# serial_port.net
KiCad netlist of a schematic drawn in Altium Designer
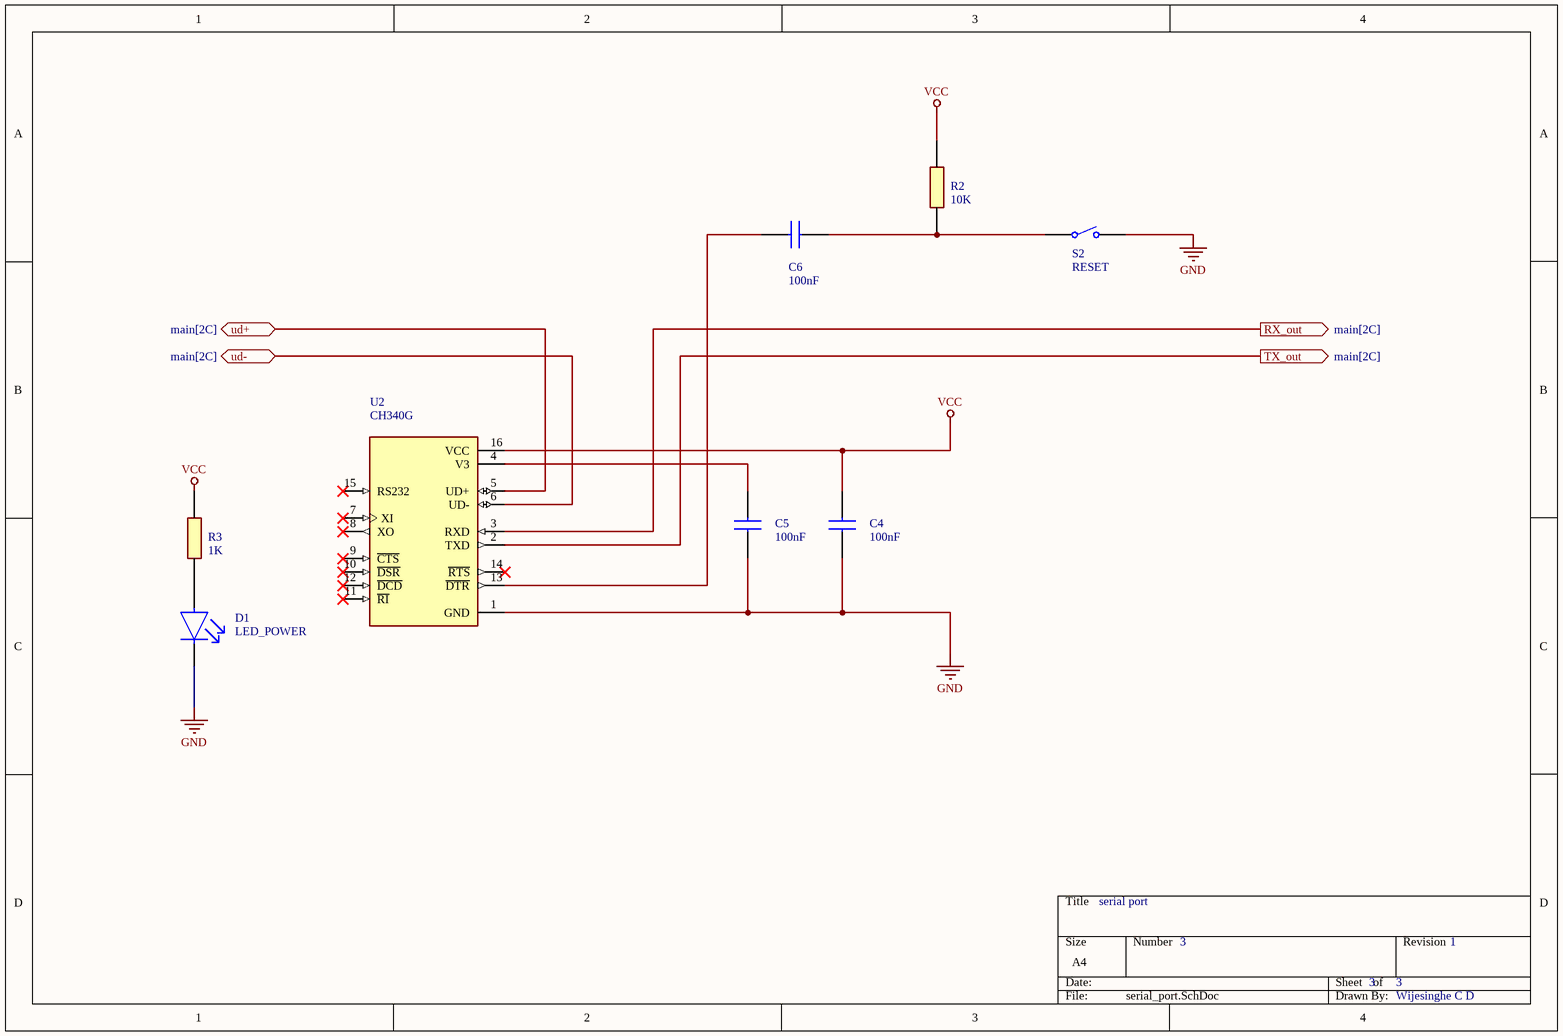
[diagram p0: serial_port.SchDoc]

(export (version "E")
  (design (tool "Eeschema 10.0.6"))
  (components
    (comp (ref "C4")
      (value "100nF")
      (footprint "SamacSys:CAPC1608X90N")
      (description "Capacitor")
      (fields
        (field (name "MANUFACTURER_PART_NUMBER") "CL10B104JB8NNNC")
        (field (name "MOUSER PART NUMBER") "187-CL10B104JB8NNNC")
      )
      (libsource (lib "*") (part "CL10B104JB8NNNC"))
    )
    (comp (ref "C5")
      (value "100nF")
      (footprint "SamacSys:CAPC1608X90N")
      (description "Capacitor")
      (fields
        (field (name "MANUFACTURER_PART_NUMBER") "CL10B104JB8NNNC")
        (field (name "MOUSER PART NUMBER") "187-CL10B104JB8NNNC")
      )
      (libsource (lib "*") (part "CL10B104JB8NNNC"))
    )
    (comp (ref "C6")
      (value "100nF")
      (footprint "SamacSys:CAPC1608X90N")
      (description "Capacitor")
      (fields
        (field (name "MANUFACTURER_PART_NUMBER") "CL10B104JB8NNNC")
        (field (name "MOUSER PART NUMBER") "187-CL10B104JB8NNNC")
      )
      (libsource (lib "*") (part "CL10B104JB8NNNC"))
    )
    (comp (ref "D1")
      (value "LED_POWER")
      (footprint "FP-LTST-C190GKT-MFG")
      (description "LED GREEN CLEAR CHIP SMD")
      (fields (field (name "VOLTAGE") "2V"))
      (libsource (lib "Altium Content Vault") (part "8706943c75ba83719d021d2fdc84c58"))
    )
    (comp (ref "R2")
      (value "10K")
      (footprint "SamacSys:RESC2012X75N")
      (description "Resistor")
      (fields
        (field (name "MANUFACTURER_PART_NUMBER") "ERJ-P6WF1002V")
        (field (name "MOUSER PART NUMBER") "667-ERJ-P6WF1002V")
      )
      (libsource (lib "*") (part "ERJ-P6WF1002V"))
    )
    (comp (ref "R3")
      (value "1K")
      (footprint "SamacSys:RESC2012X75N")
      (description "Resistor")
      (fields
        (field (name "MANUFACTURER_PART_NUMBER") "ERJ-P6WF1002V")
        (field (name "MOUSER PART NUMBER") "667-ERJ-P6WF1002V")
      )
      (libsource (lib "*") (part "ERJ-P6WF1002V"))
    )
    (comp (ref "S2")
      (value "RESET")
      (footprint "TECO-FSMSM-2_V")
      (description "FSMSM Push Button Switch, 50 mA, -35 to 85 degC, 2-Pin SMD, RoHS, Bulk")
      (fields (field (name "MANUFACTURER") "TE Connectivity"))
      (libsource (lib "Altium Content Vault") (part "SW-SPST-2_C"))
    )
    (comp (ref "U2")
      (value "CH340G")
      (footprint "SOIC127P600X180-16N")
      (description "USB Interface Integrated Circuit")
      (fields (field (name "MP") "Ch340G") (field (name "MF") "WCH"))
      (libsource (lib "CH340G") (part "CH340G"))
    )
  )
  (nets
    (net (code "1") (name "/RX_out") (class "Default")
      (node (ref "U2") (pin "3") (pinfunction "RXD_3") (pintype "input"))
    )
    (net (code "2") (name "/TX_out") (class "Default")
      (node (ref "U2") (pin "2") (pinfunction "TXD_2") (pintype "output"))
    )
    (net (code "3") (name "/ud+") (class "Default")
      (node (ref "U2") (pin "5") (pinfunction "UD+_5") (pintype "bidirectional"))
    )
    (net (code "4") (name "/ud-") (class "Default")
      (node (ref "U2") (pin "6") (pinfunction "UD-_6") (pintype "bidirectional"))
    )
    (net (code "5") (name "GND") (class "Default")
      (node (ref "C4") (pin "2") (pinfunction "2_2") (pintype "passive"))
      (node (ref "C5") (pin "2") (pinfunction "2_2") (pintype "passive"))
      (node (ref "D1") (pin "1") (pinfunction "C_1") (pintype "passive"))
      (node (ref "S2") (pin "2") (pinfunction "2_2") (pintype "passive"))
      (node (ref "U2") (pin "1") (pinfunction "GND_1") (pintype "power_in"))
    )
    (net (code "6") (name "Net-(C6-Pad2)") (class "Default")
      (node (ref "C6") (pin "2") (pinfunction "2_2") (pintype "passive"))
      (node (ref "R2") (pin "1") (pinfunction "1_1") (pintype "passive"))
      (node (ref "S2") (pin "1") (pinfunction "1_1") (pintype "passive"))
    )
    (net (code "7") (name "Net-(D1-A)") (class "Default")
      (node (ref "D1") (pin "2") (pinfunction "A_2") (pintype "passive"))
      (node (ref "R3") (pin "1") (pinfunction "1_1") (pintype "passive"))
    )
    (net (code "8") (name "Net-(U2-V3)") (class "Default")
      (node (ref "C5") (pin "1") (pinfunction "1_1") (pintype "passive"))
      (node (ref "U2") (pin "4") (pinfunction "V3_4") (pintype "power_in"))
    )
    (net (code "9") (name "Net-(U2-~{DTR})") (class "Default")
      (node (ref "C6") (pin "1") (pinfunction "1_1") (pintype "passive"))
      (node (ref "U2") (pin "13") (pinfunction "~{DTR}_13") (pintype "output"))
    )
    (net (code "10") (name "VCC") (class "Default")
      (node (ref "C4") (pin "1") (pinfunction "1_1") (pintype "passive"))
      (node (ref "R2") (pin "2") (pinfunction "2_2") (pintype "passive"))
      (node (ref "R3") (pin "2") (pinfunction "2_2") (pintype "passive"))
      (node (ref "U2") (pin "16") (pinfunction "VCC_16") (pintype "power_in"))
    )
    (net (code "11") (name "unconnected-(U2-RS232-Pad15)") (class "Default")
      (node (ref "U2") (pin "15") (pinfunction "RS232_15") (pintype "input+no_connect"))
    )
    (net (code "12") (name "unconnected-(U2-XI-Pad7)") (class "Default")
      (node (ref "U2") (pin "7") (pinfunction "XI_7") (pintype "input+no_connect"))
    )
    (net (code "13") (name "unconnected-(U2-XO-Pad8)") (class "Default")
      (node (ref "U2") (pin "8") (pinfunction "XO_8") (pintype "output+no_connect"))
    )
    (net (code "14") (name "unconnected-(U2-~{CTS}-Pad9)") (class "Default")
      (node (ref "U2") (pin "9") (pinfunction "~{CTS}_9") (pintype "input+no_connect"))
    )
    (net (code "15") (name "unconnected-(U2-~{DCD}-Pad12)") (class "Default")
      (node (ref "U2") (pin "12") (pinfunction "~{DCD}_12") (pintype "input+no_connect"))
    )
    (net (code "16") (name "unconnected-(U2-~{DSR}-Pad10)") (class "Default")
      (node (ref "U2") (pin "10") (pinfunction "~{DSR}_10") (pintype "input+no_connect"))
    )
    (net (code "17") (name "unconnected-(U2-~{RI}-Pad11)") (class "Default")
      (node (ref "U2") (pin "11") (pinfunction "~{RI}_11") (pintype "input+no_connect"))
    )
    (net (code "18") (name "unconnected-(U2-~{RTS}-Pad14)") (class "Default")
      (node (ref "U2") (pin "14") (pinfunction "~{RTS}_14") (pintype "output+no_connect"))
    )
  )
)
